# design.net
KiCad netlist of a schematic drawn in EasyEDA Pro
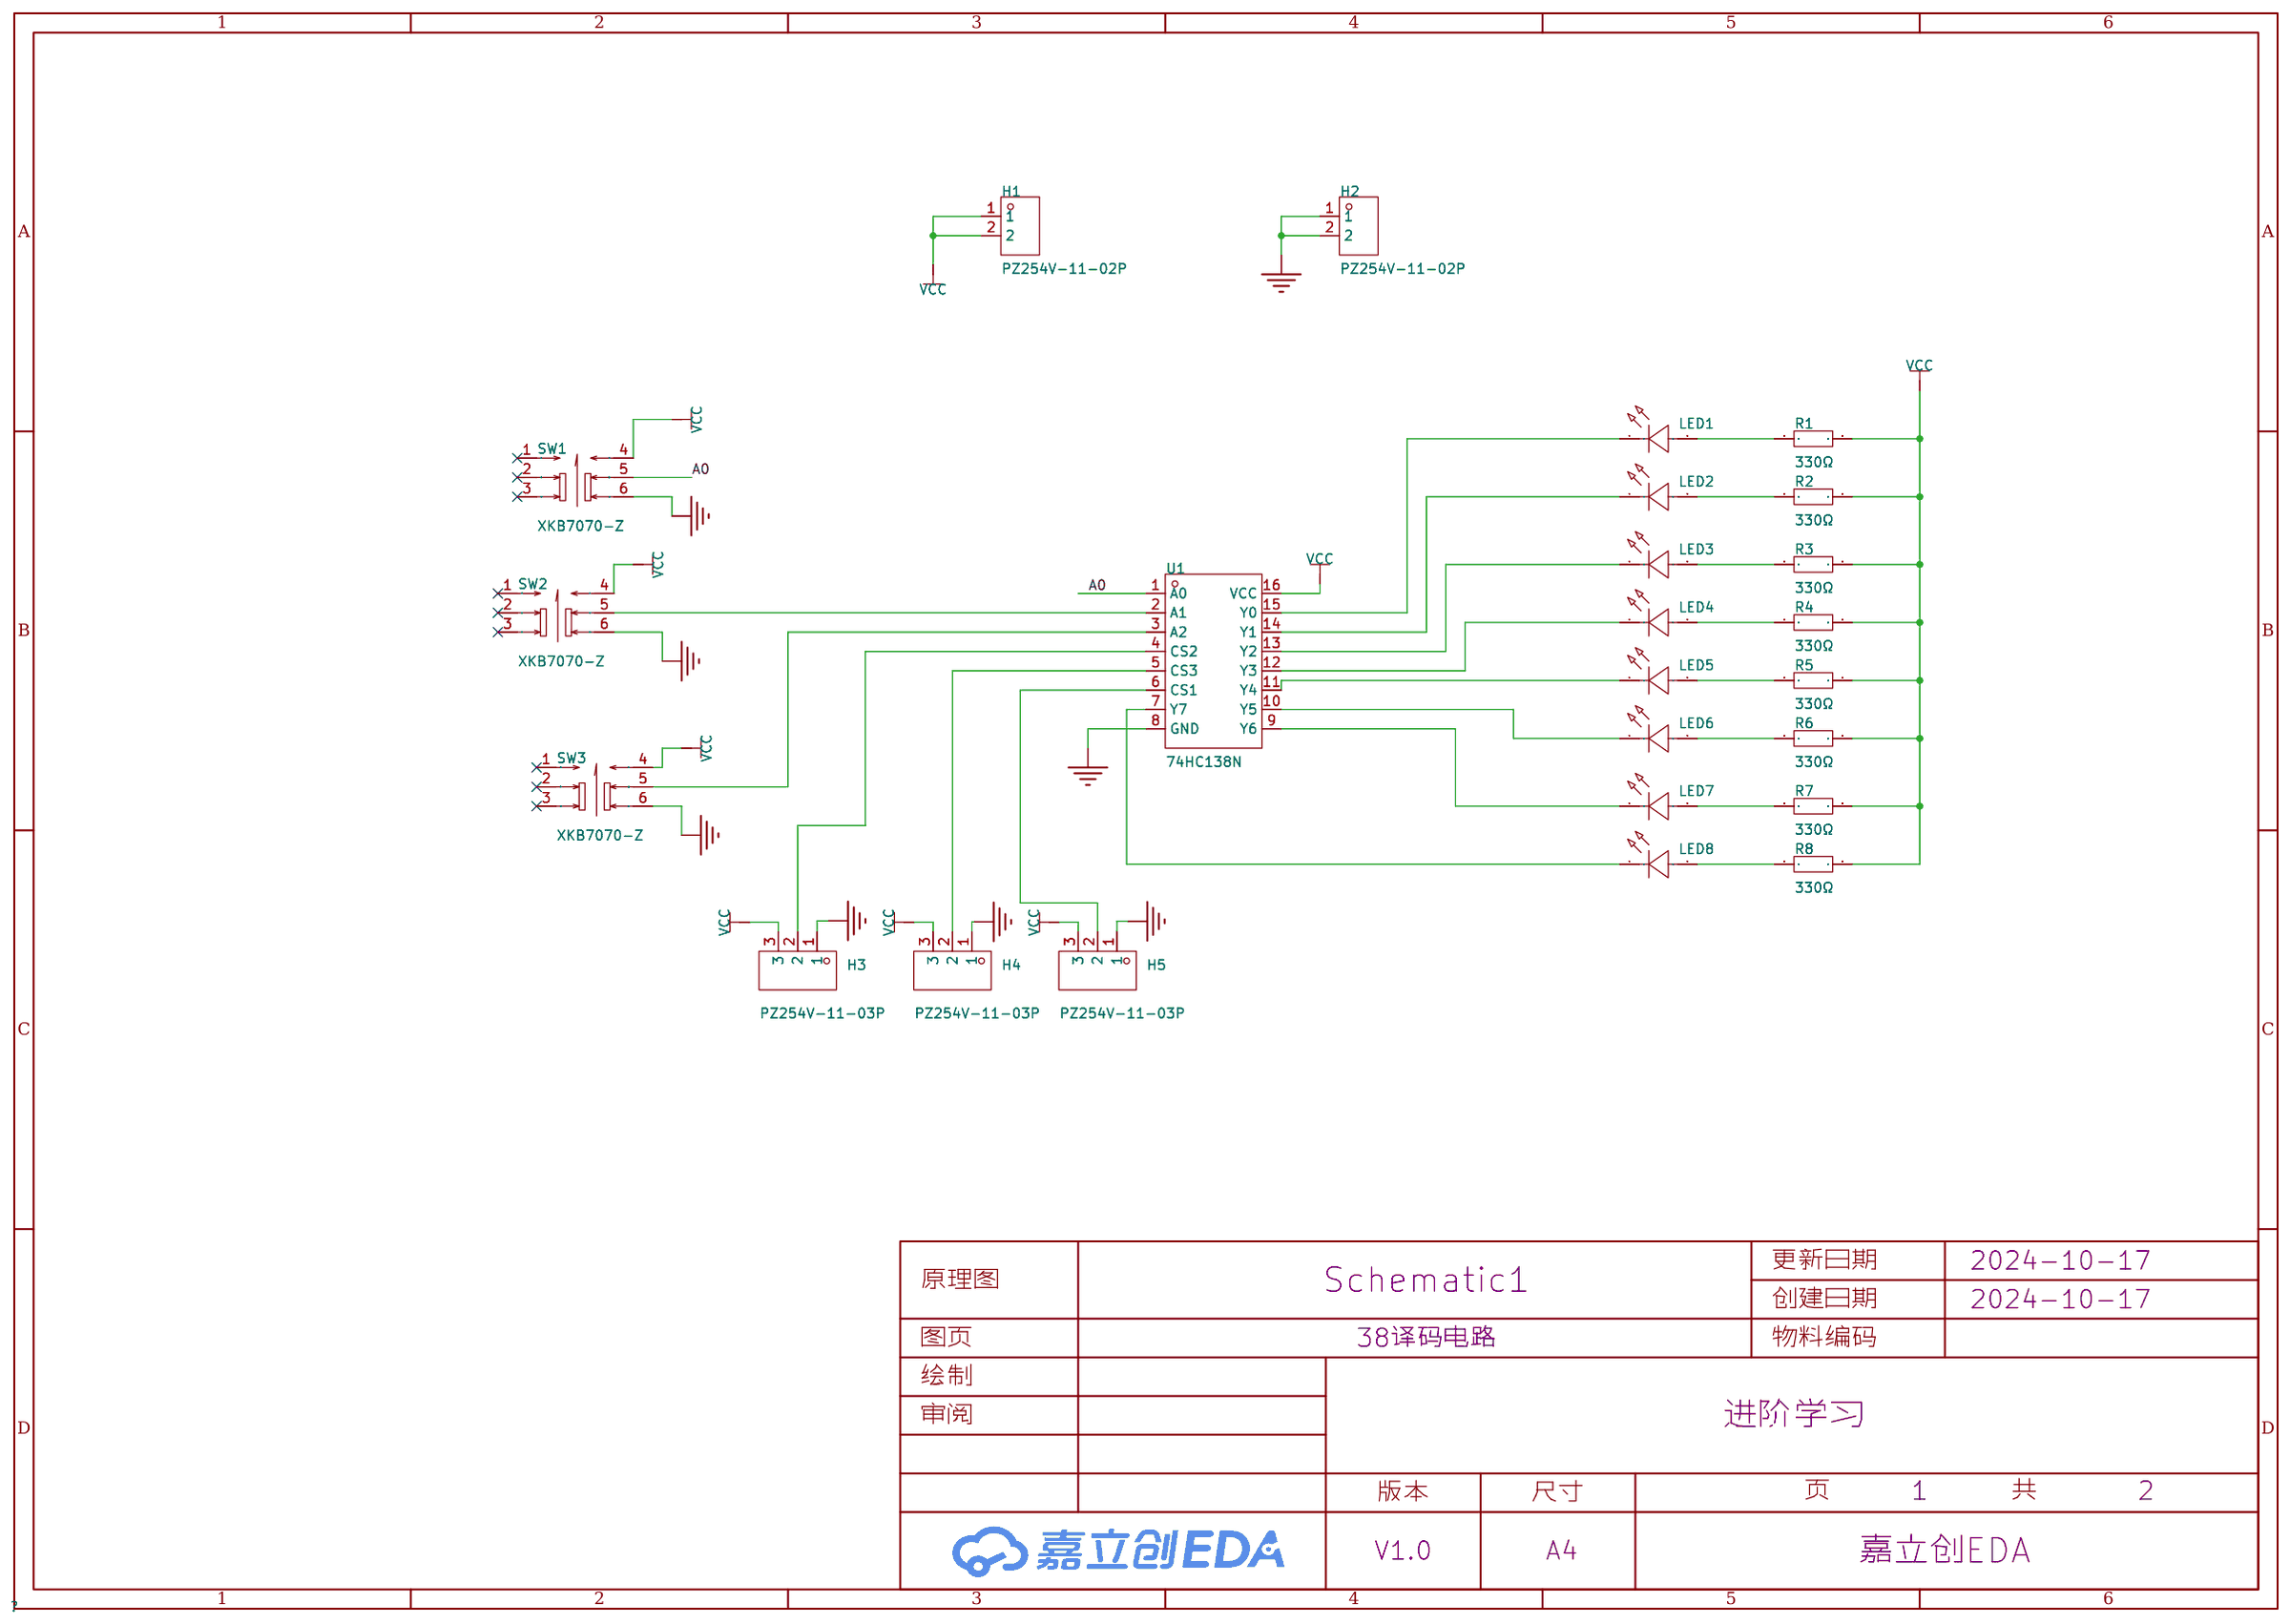
[diagram p0: 38译码电路]
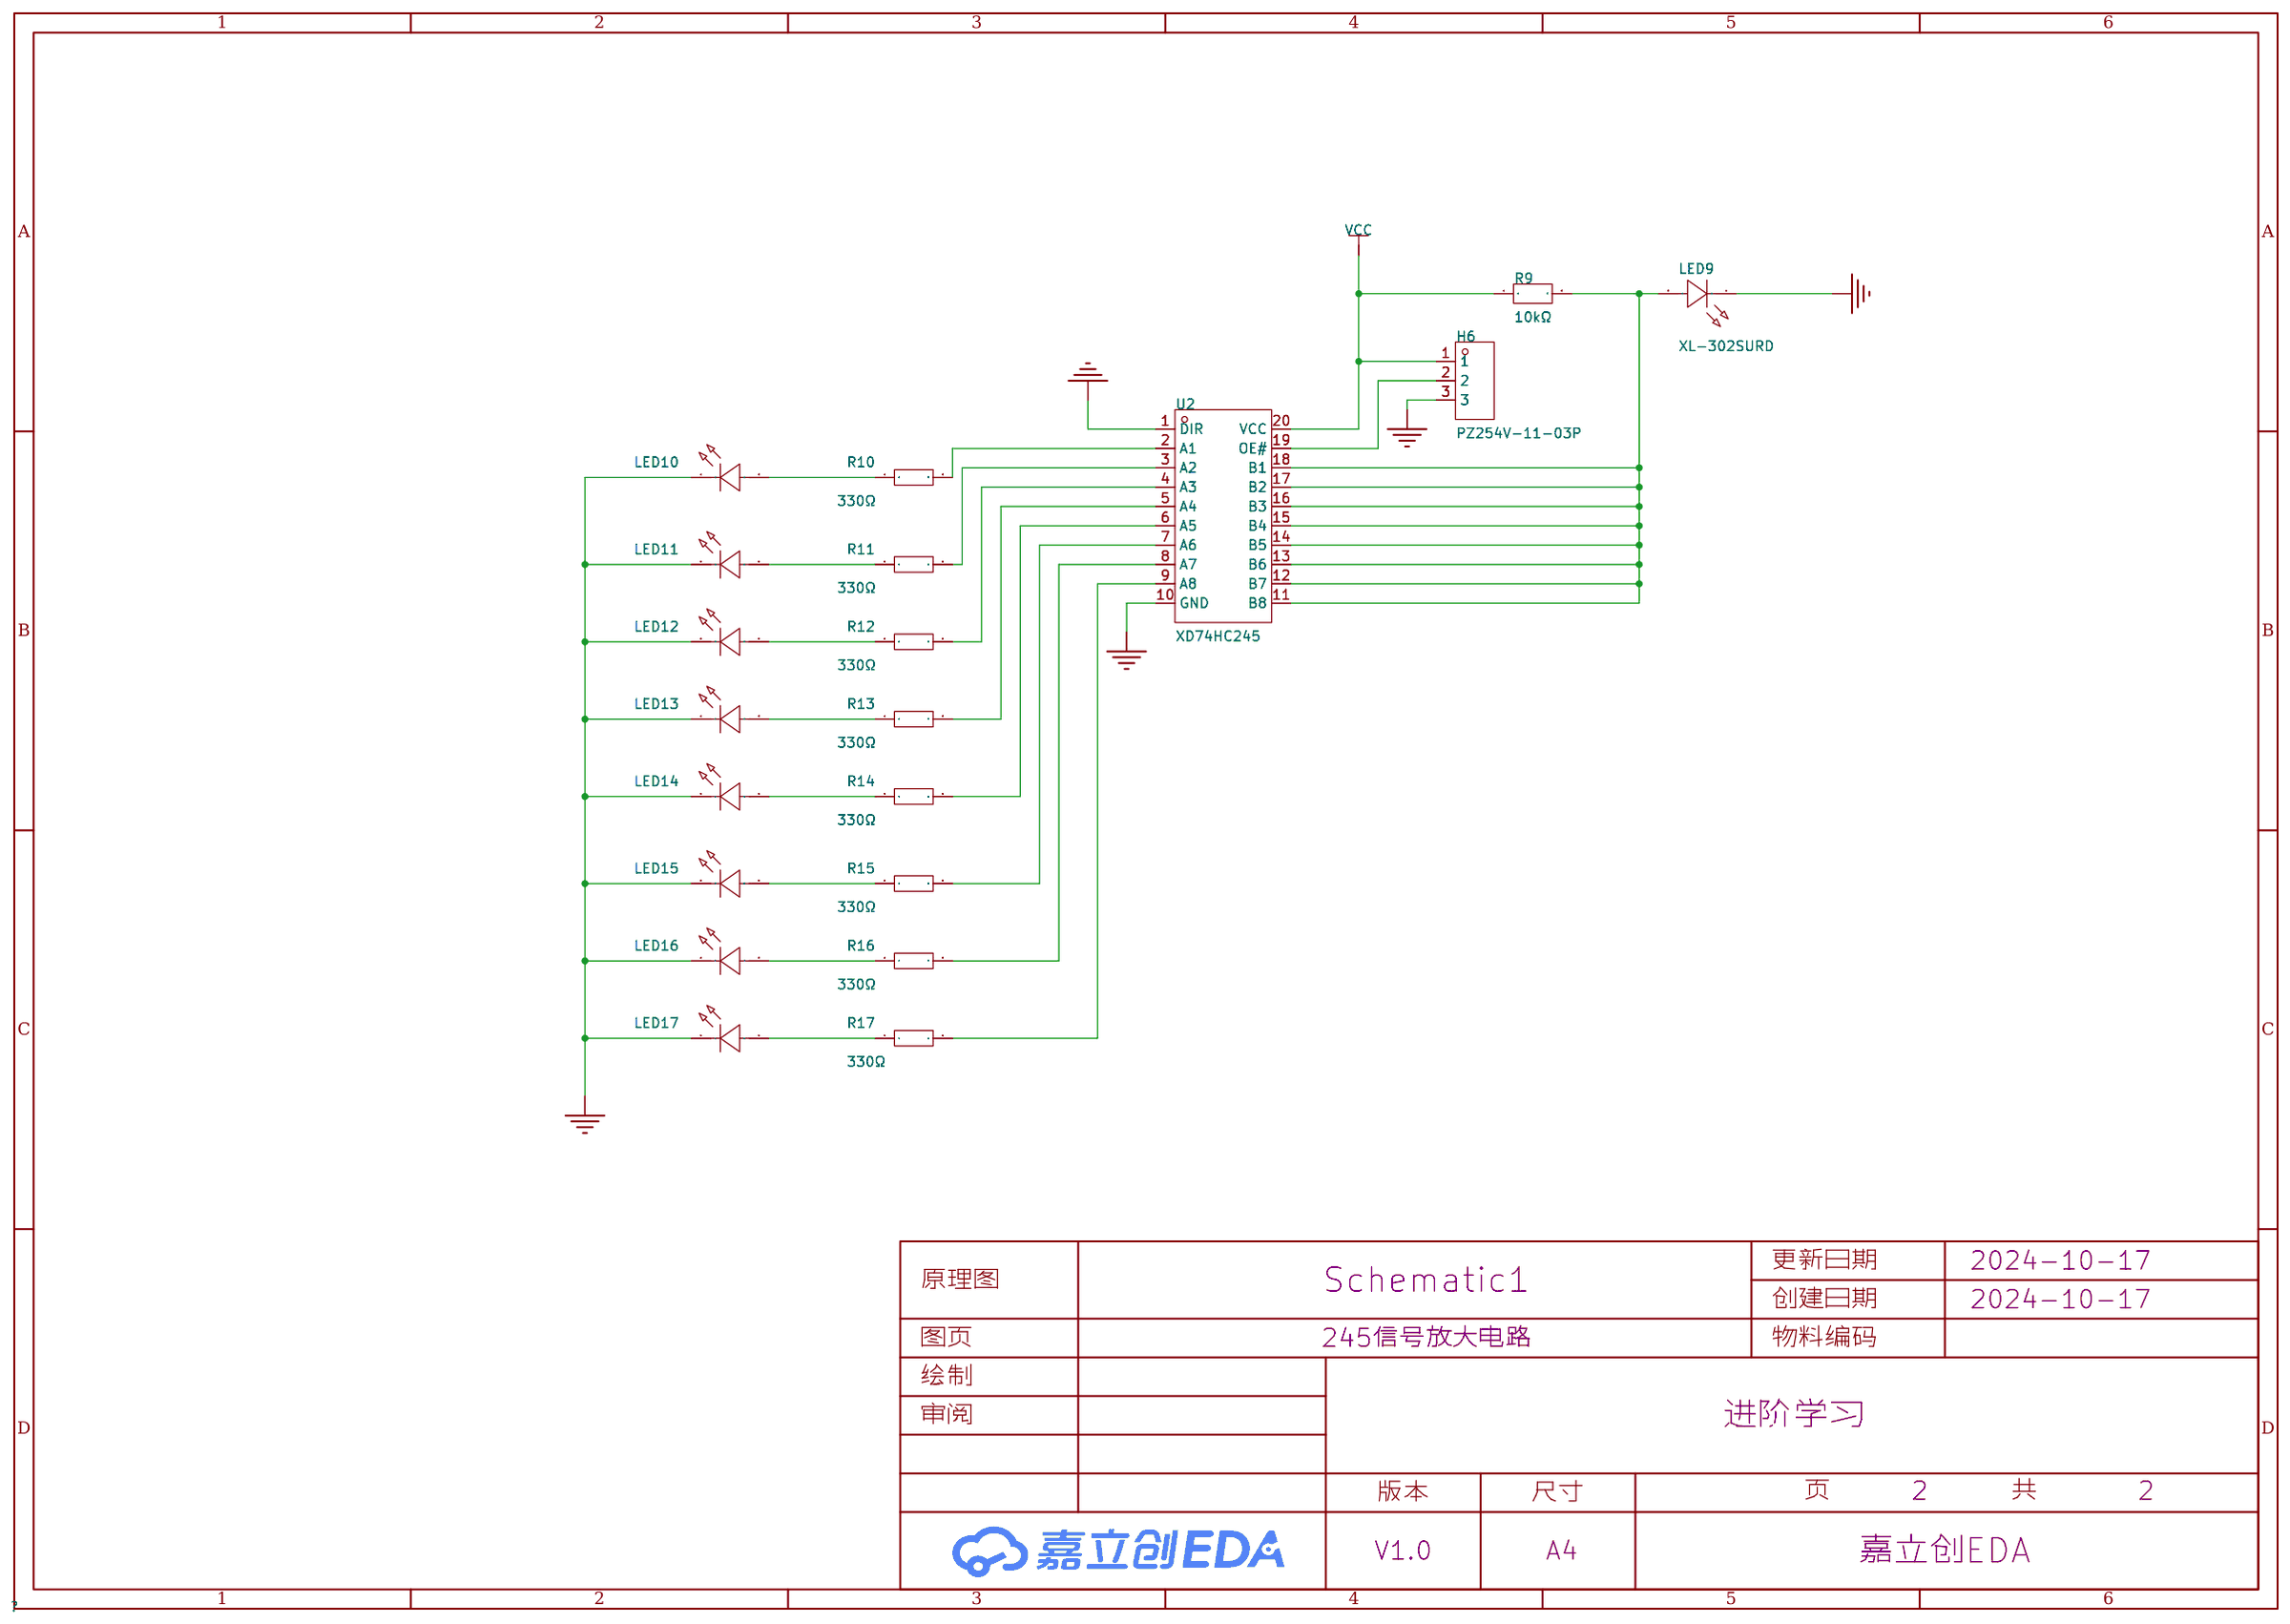
[diagram p1: 245信号放大电路]
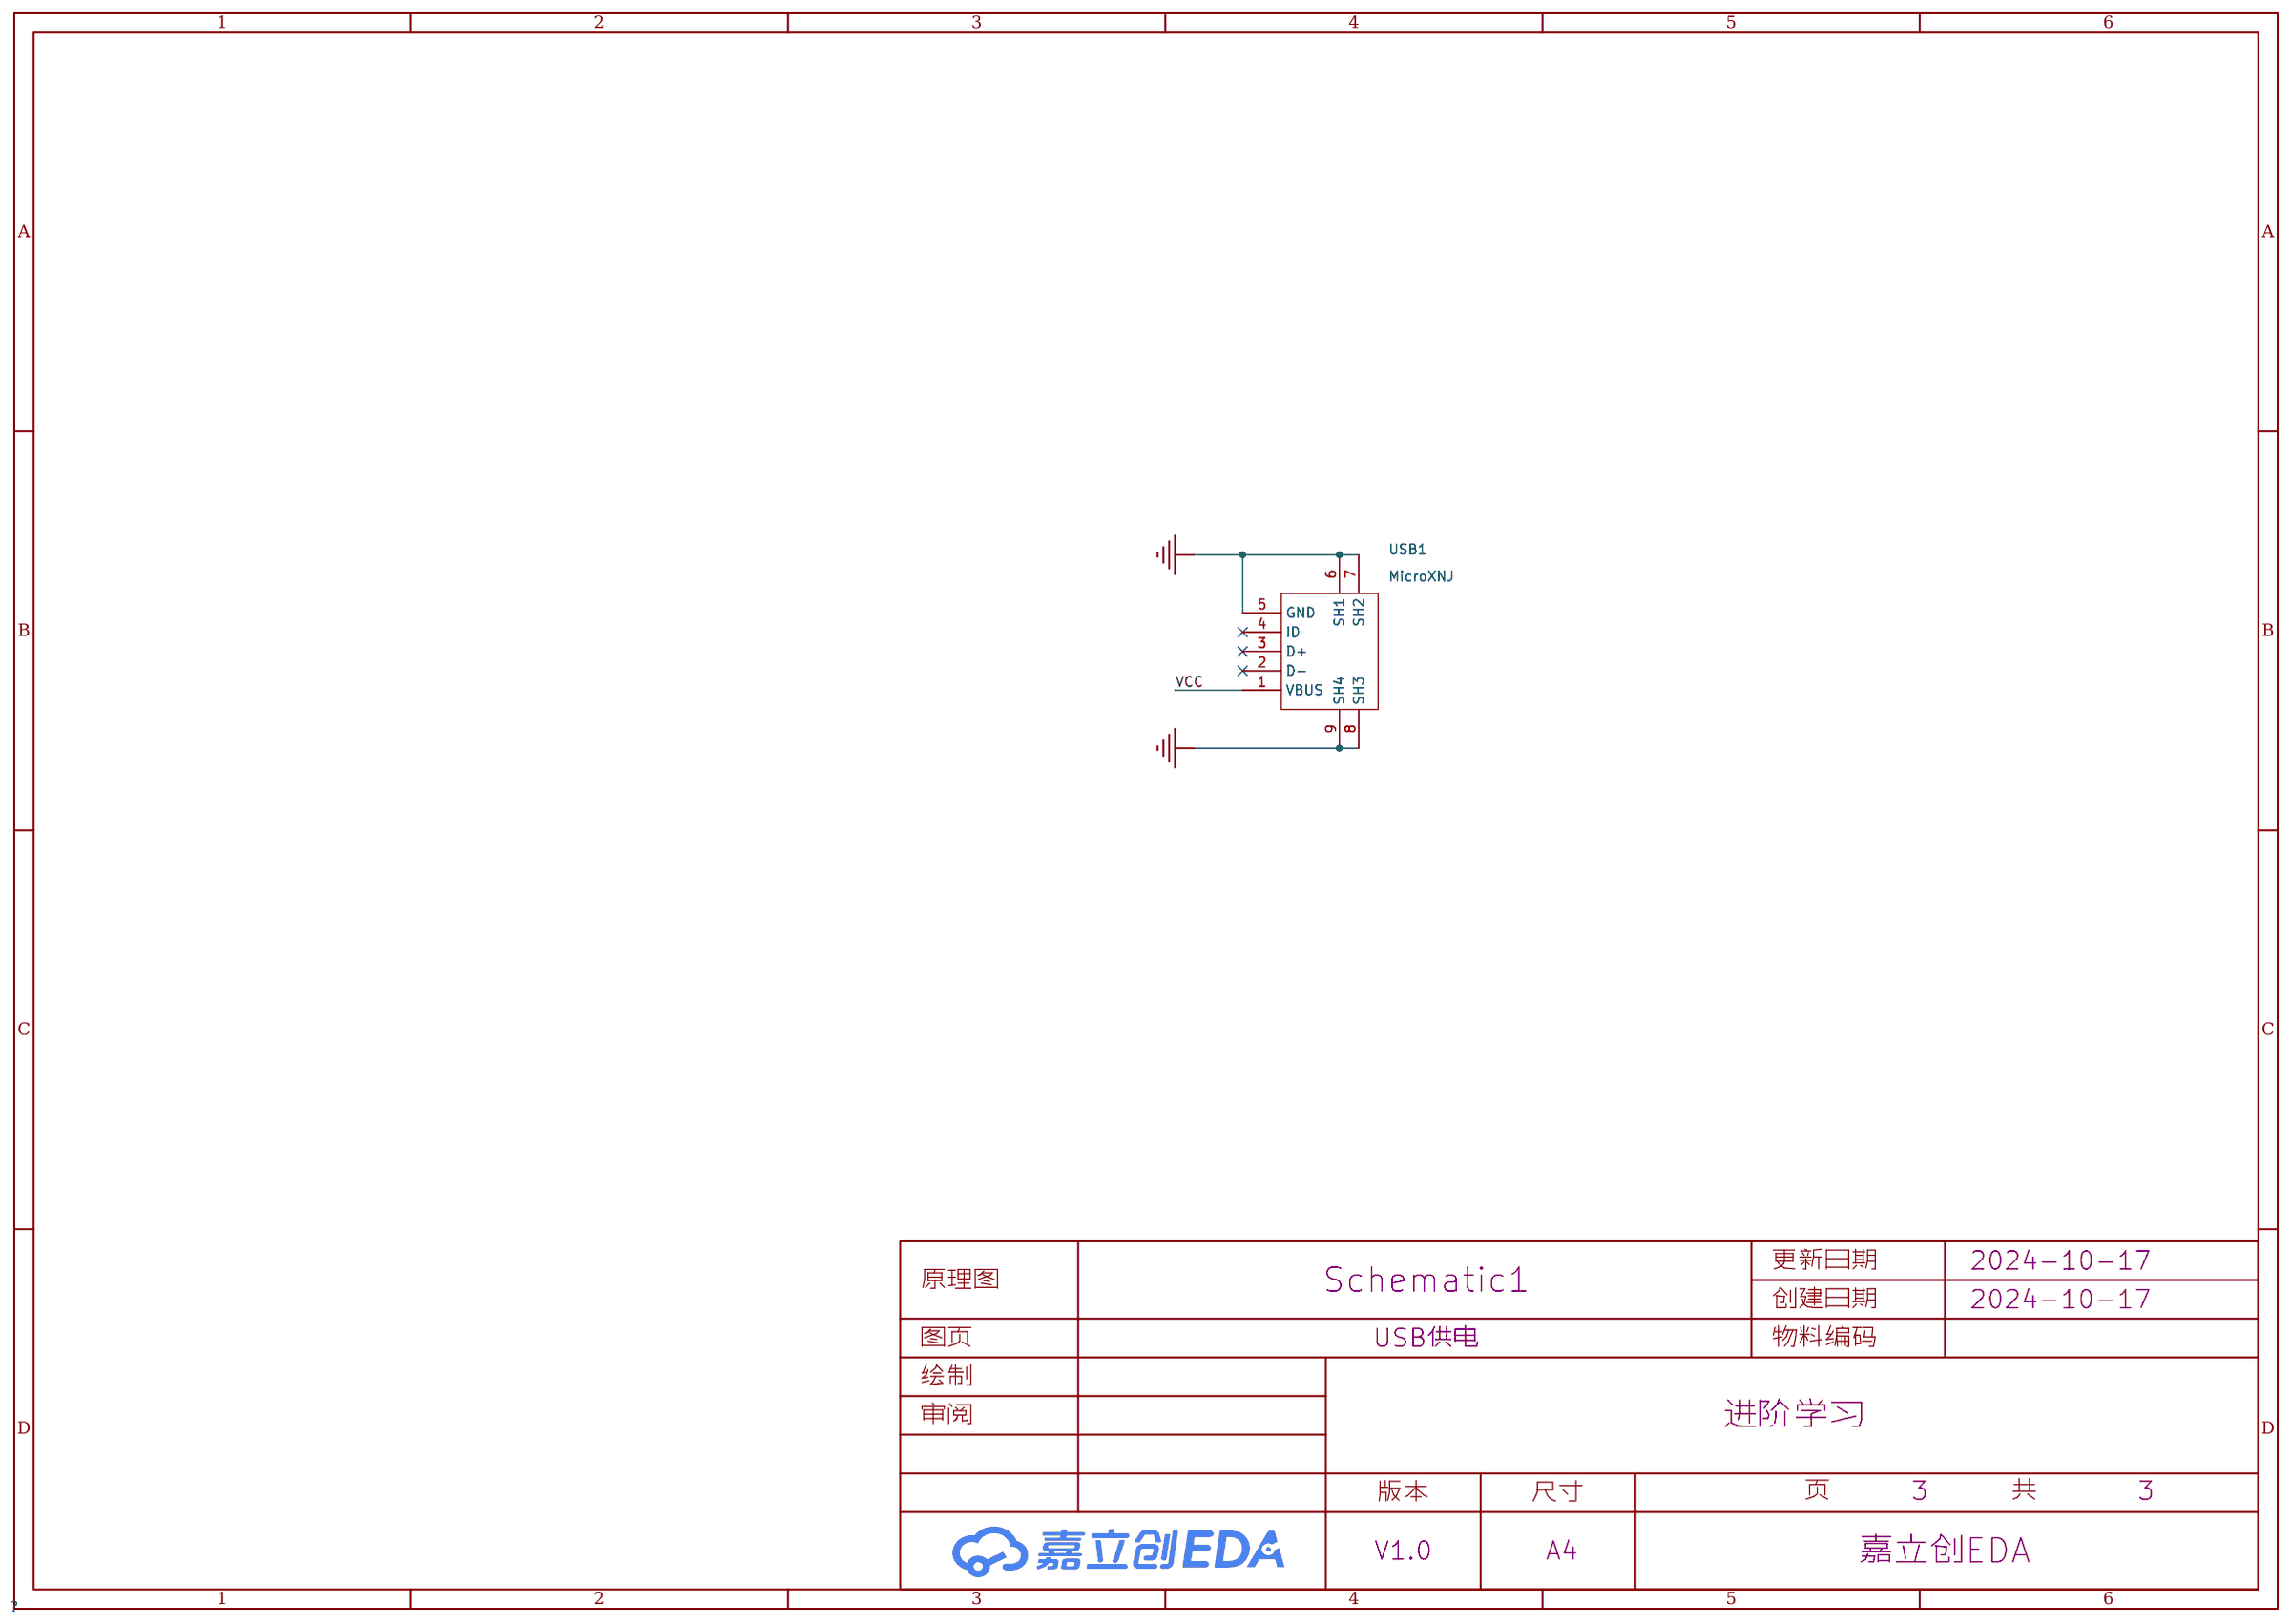
[diagram p2: USB供电]

(export (version "E")
  (design (tool "Eeschema 10.0.6"))
  (components
    (comp (ref "H1")
      (value "PZ254V-11-02P")
      (footprint "easyedapro:HDR-TH_2P-P2.54-V-M")
      (fields (field (name "Manufacturer") "XFCN(兴飞)"))
      (libsource (lib "easyedapro") (part "PZ254V-11-02P"))
    )
    (comp (ref "H2")
      (value "PZ254V-11-02P")
      (footprint "easyedapro:HDR-TH_2P-P2.54-V-M")
      (fields (field (name "Manufacturer") "XFCN(兴飞)"))
      (libsource (lib "easyedapro") (part "PZ254V-11-02P"))
    )
    (comp (ref "H3")
      (value "PZ254V-11-03P")
      (footprint "easyedapro:HDR-TH_3P-P2.54-V-M")
      (fields (field (name "Manufacturer") "XFCN(兴飞)"))
      (libsource (lib "easyedapro") (part "PZ254V-11-03P_C2937625"))
    )
    (comp (ref "H4")
      (value "PZ254V-11-03P")
      (footprint "easyedapro:HDR-TH_3P-P2.54-V-M")
      (fields (field (name "Manufacturer") "XFCN(兴飞)"))
      (libsource (lib "easyedapro") (part "PZ254V-11-03P_C2937625"))
    )
    (comp (ref "H5")
      (value "PZ254V-11-03P")
      (footprint "easyedapro:HDR-TH_3P-P2.54-V-M")
      (fields (field (name "Manufacturer") "XFCN(兴飞)"))
      (libsource (lib "easyedapro") (part "PZ254V-11-03P_C2937625"))
    )
    (comp (ref "LED1")
      (value "XL-302SURD")
      (footprint "easyedapro:LED-TH_BD3.8-P2.54-RD")
      (fields (field (name "Manufacturer") "XINGLIGHT(成兴光)"))
      (libsource (lib "easyedapro") (part "XL-302SURD"))
    )
    (comp (ref "LED2")
      (value "XL-302SURD")
      (footprint "easyedapro:LED-TH_BD3.8-P2.54-RD")
      (fields (field (name "Manufacturer") "XINGLIGHT(成兴光)"))
      (libsource (lib "easyedapro") (part "XL-302SURD"))
    )
    (comp (ref "LED3")
      (value "XL-302SURD")
      (footprint "easyedapro:LED-TH_BD3.8-P2.54-RD")
      (fields (field (name "Manufacturer") "XINGLIGHT(成兴光)"))
      (libsource (lib "easyedapro") (part "XL-302SURD"))
    )
    (comp (ref "LED4")
      (value "XL-302SURD")
      (footprint "easyedapro:LED-TH_BD3.8-P2.54-RD")
      (fields (field (name "Manufacturer") "XINGLIGHT(成兴光)"))
      (libsource (lib "easyedapro") (part "XL-302SURD"))
    )
    (comp (ref "LED5")
      (value "XL-302SURD")
      (footprint "easyedapro:LED-TH_BD3.8-P2.54-RD")
      (fields (field (name "Manufacturer") "XINGLIGHT(成兴光)"))
      (libsource (lib "easyedapro") (part "XL-302SURD"))
    )
    (comp (ref "LED6")
      (value "XL-302SURD")
      (footprint "easyedapro:LED-TH_BD3.8-P2.54-RD")
      (fields (field (name "Manufacturer") "XINGLIGHT(成兴光)"))
      (libsource (lib "easyedapro") (part "XL-302SURD"))
    )
    (comp (ref "LED7")
      (value "XL-302SURD")
      (footprint "easyedapro:LED-TH_BD3.8-P2.54-RD")
      (fields (field (name "Manufacturer") "XINGLIGHT(成兴光)"))
      (libsource (lib "easyedapro") (part "XL-302SURD"))
    )
    (comp (ref "LED8")
      (value "XL-302SURD")
      (footprint "easyedapro:LED-TH_BD3.8-P2.54-RD")
      (fields (field (name "Manufacturer") "XINGLIGHT(成兴光)"))
      (libsource (lib "easyedapro") (part "XL-302SURD"))
    )
    (comp (ref "R1")
      (value "330Ω")
      (footprint "easyedapro:RES-TH_BD2.3-L3.7-P7.70-D0.9")
      (description "电阻类型:金属膜电阻;阻值:330Ω;精度:±1%;功率:125mW;温度系数:±350ppm/°C;")
      (fields (field (name "Manufacturer Part") "MF1/8W-330Ω±1%-OT52") (field (name "Manufacturer") "VO(翔胜)"))
      (libsource (lib "easyedapro") (part "MF1/8W-330Ω±1%-OT52"))
    )
    (comp (ref "R2")
      (value "330Ω")
      (footprint "easyedapro:RES-TH_BD2.3-L3.7-P7.70-D0.9")
      (description "电阻类型:金属膜电阻;阻值:330Ω;精度:±1%;功率:125mW;温度系数:±350ppm/°C;")
      (fields (field (name "Manufacturer Part") "MF1/8W-330Ω±1%-OT52") (field (name "Manufacturer") "VO(翔胜)"))
      (libsource (lib "easyedapro") (part "MF1/8W-330Ω±1%-OT52"))
    )
    (comp (ref "R3")
      (value "330Ω")
      (footprint "easyedapro:RES-TH_BD2.3-L3.7-P7.70-D0.9")
      (description "电阻类型:金属膜电阻;阻值:330Ω;精度:±1%;功率:125mW;温度系数:±350ppm/°C;")
      (fields (field (name "Manufacturer Part") "MF1/8W-330Ω±1%-OT52") (field (name "Manufacturer") "VO(翔胜)"))
      (libsource (lib "easyedapro") (part "MF1/8W-330Ω±1%-OT52"))
    )
    (comp (ref "R4")
      (value "330Ω")
      (footprint "easyedapro:RES-TH_BD2.3-L3.7-P7.70-D0.9")
      (description "电阻类型:金属膜电阻;阻值:330Ω;精度:±1%;功率:125mW;温度系数:±350ppm/°C;")
      (fields (field (name "Manufacturer Part") "MF1/8W-330Ω±1%-OT52") (field (name "Manufacturer") "VO(翔胜)"))
      (libsource (lib "easyedapro") (part "MF1/8W-330Ω±1%-OT52"))
    )
    (comp (ref "R5")
      (value "330Ω")
      (footprint "easyedapro:RES-TH_BD2.3-L3.7-P7.70-D0.9")
      (description "电阻类型:金属膜电阻;阻值:330Ω;精度:±1%;功率:125mW;温度系数:±350ppm/°C;")
      (fields (field (name "Manufacturer Part") "MF1/8W-330Ω±1%-OT52") (field (name "Manufacturer") "VO(翔胜)"))
      (libsource (lib "easyedapro") (part "MF1/8W-330Ω±1%-OT52"))
    )
    (comp (ref "R6")
      (value "330Ω")
      (footprint "easyedapro:RES-TH_BD2.3-L3.7-P7.70-D0.9")
      (description "电阻类型:金属膜电阻;阻值:330Ω;精度:±1%;功率:125mW;温度系数:±350ppm/°C;")
      (fields (field (name "Manufacturer Part") "MF1/8W-330Ω±1%-OT52") (field (name "Manufacturer") "VO(翔胜)"))
      (libsource (lib "easyedapro") (part "MF1/8W-330Ω±1%-OT52"))
    )
    (comp (ref "R7")
      (value "330Ω")
      (footprint "easyedapro:RES-TH_BD2.3-L3.7-P7.70-D0.9")
      (description "电阻类型:金属膜电阻;阻值:330Ω;精度:±1%;功率:125mW;温度系数:±350ppm/°C;")
      (fields (field (name "Manufacturer Part") "MF1/8W-330Ω±1%-OT52") (field (name "Manufacturer") "VO(翔胜)"))
      (libsource (lib "easyedapro") (part "MF1/8W-330Ω±1%-OT52"))
    )
    (comp (ref "R8")
      (value "330Ω")
      (footprint "easyedapro:RES-TH_BD2.3-L3.7-P7.70-D0.9")
      (description "电阻类型:金属膜电阻;阻值:330Ω;精度:±1%;功率:125mW;温度系数:±350ppm/°C;")
      (fields (field (name "Manufacturer Part") "MF1/8W-330Ω±1%-OT52") (field (name "Manufacturer") "VO(翔胜)"))
      (libsource (lib "easyedapro") (part "MF1/8W-330Ω±1%-OT52"))
    )
    (comp (ref "SW1")
      (value "XKB7070-Z")
      (footprint "easyedapro:SW-TH_6P-L7.0-W7.0-P2.00")
      (description "自锁/无锁:自锁;安装方式:直插;触点电流:100mA;额定电压 (AC):250V;额定电压 (DC):30V;带灯:不带;作用力:160gf;机械寿命:10万次;")
      (fields (field (name "Manufacturer") "XKB Connectivity(中国星坤)"))
      (libsource (lib "easyedapro") (part "XKB7070-Z"))
    )
    (comp (ref "SW2")
      (value "XKB7070-Z")
      (footprint "easyedapro:SW-TH_6P-L7.0-W7.0-P2.00")
      (description "自锁/无锁:自锁;安装方式:直插;触点电流:100mA;额定电压 (AC):250V;额定电压 (DC):30V;带灯:不带;作用力:160gf;机械寿命:10万次;")
      (fields (field (name "Manufacturer") "XKB Connectivity(中国星坤)"))
      (libsource (lib "easyedapro") (part "XKB7070-Z"))
    )
    (comp (ref "SW3")
      (value "XKB7070-Z")
      (footprint "easyedapro:SW-TH_6P-L7.0-W7.0-P2.00")
      (description "自锁/无锁:自锁;安装方式:直插;触点电流:100mA;额定电压 (AC):250V;额定电压 (DC):30V;带灯:不带;作用力:160gf;机械寿命:10万次;")
      (fields (field (name "Manufacturer") "XKB Connectivity(中国星坤)"))
      (libsource (lib "easyedapro") (part "XKB7070-Z"))
    )
    (comp (ref "U1")
      (value "74HC138N")
      (footprint "easyedapro:DIP-16_L19.2-W6.6-P2.54-LS7.6-BL")
      (fields (field (name "Manufacturer") "HGSEMI(华冠)"))
      (libsource (lib "easyedapro") (part "74HC138N"))
    )
    (comp (ref "H6")
      (value "PZ254V-11-03P")
      (footprint "easyedapro:HDR-TH_3P-P2.54-V-M")
      (fields (field (name "Manufacturer") "XFCN(兴飞)"))
      (libsource (lib "easyedapro") (part "PZ254V-11-03P_C2937625"))
    )
    (comp (ref "LED9")
      (value "XL-302SURD")
      (footprint "easyedapro:LED-TH_BD3.8-P2.54-RD")
      (fields (field (name "Manufacturer") "XINGLIGHT(成兴光)"))
      (libsource (lib "easyedapro") (part "XL-302SURD"))
    )
    (comp (ref "LED10")
      (value "XL-302SURD")
      (footprint "easyedapro:LED-TH_BD3.8-P2.54-RD")
      (fields (field (name "Manufacturer") "XINGLIGHT(成兴光)"))
      (libsource (lib "easyedapro") (part "XL-302SURD"))
    )
    (comp (ref "LED11")
      (value "XL-302SURD")
      (footprint "easyedapro:LED-TH_BD3.8-P2.54-RD")
      (fields (field (name "Manufacturer") "XINGLIGHT(成兴光)"))
      (libsource (lib "easyedapro") (part "XL-302SURD"))
    )
    (comp (ref "LED12")
      (value "XL-302SURD")
      (footprint "easyedapro:LED-TH_BD3.8-P2.54-RD")
      (fields (field (name "Manufacturer") "XINGLIGHT(成兴光)"))
      (libsource (lib "easyedapro") (part "XL-302SURD"))
    )
    (comp (ref "LED13")
      (value "XL-302SURD")
      (footprint "easyedapro:LED-TH_BD3.8-P2.54-RD")
      (fields (field (name "Manufacturer") "XINGLIGHT(成兴光)"))
      (libsource (lib "easyedapro") (part "XL-302SURD"))
    )
    (comp (ref "LED14")
      (value "XL-302SURD")
      (footprint "easyedapro:LED-TH_BD3.8-P2.54-RD")
      (fields (field (name "Manufacturer") "XINGLIGHT(成兴光)"))
      (libsource (lib "easyedapro") (part "XL-302SURD"))
    )
    (comp (ref "LED15")
      (value "XL-302SURD")
      (footprint "easyedapro:LED-TH_BD3.8-P2.54-RD")
      (fields (field (name "Manufacturer") "XINGLIGHT(成兴光)"))
      (libsource (lib "easyedapro") (part "XL-302SURD"))
    )
    (comp (ref "LED16")
      (value "XL-302SURD")
      (footprint "easyedapro:LED-TH_BD3.8-P2.54-RD")
      (fields (field (name "Manufacturer") "XINGLIGHT(成兴光)"))
      (libsource (lib "easyedapro") (part "XL-302SURD"))
    )
    (comp (ref "LED17")
      (value "XL-302SURD")
      (footprint "easyedapro:LED-TH_BD3.8-P2.54-RD")
      (fields (field (name "Manufacturer") "XINGLIGHT(成兴光)"))
      (libsource (lib "easyedapro") (part "XL-302SURD"))
    )
    (comp (ref "R9")
      (value "10kΩ")
      (footprint "easyedapro:RES-TH_BD1.8-L3.2-P7.20-D0.4")
      (description "电阻类型:金属膜电阻;阻值:10kΩ;精度:±1%;功率:125mW;温度系数:±200ppm/°C;")
      (fields (field (name "Manufacturer Part") "MF1/8W-10KΩ±1%T52") (field (name "Manufacturer") "华星机电"))
      (libsource (lib "easyedapro") (part "MF1/8W-10KΩ±1%T52"))
    )
    (comp (ref "R10")
      (value "330Ω")
      (footprint "easyedapro:RES-TH_BD2.3-L3.7-P7.70-D0.9")
      (description "电阻类型:金属膜电阻;阻值:330Ω;精度:±1%;功率:125mW;温度系数:±350ppm/°C;")
      (fields (field (name "Manufacturer Part") "MF1/8W-330Ω±1%-OT52") (field (name "Manufacturer") "VO(翔胜)"))
      (libsource (lib "easyedapro") (part "MF1/8W-330Ω±1%-OT52"))
    )
    (comp (ref "R11")
      (value "330Ω")
      (footprint "easyedapro:RES-TH_BD2.3-L3.7-P7.70-D0.9")
      (description "电阻类型:金属膜电阻;阻值:330Ω;精度:±1%;功率:125mW;温度系数:±350ppm/°C;")
      (fields (field (name "Manufacturer Part") "MF1/8W-330Ω±1%-OT52") (field (name "Manufacturer") "VO(翔胜)"))
      (libsource (lib "easyedapro") (part "MF1/8W-330Ω±1%-OT52"))
    )
    (comp (ref "R12")
      (value "330Ω")
      (footprint "easyedapro:RES-TH_BD2.3-L3.7-P7.70-D0.9")
      (description "电阻类型:金属膜电阻;阻值:330Ω;精度:±1%;功率:125mW;温度系数:±350ppm/°C;")
      (fields (field (name "Manufacturer Part") "MF1/8W-330Ω±1%-OT52") (field (name "Manufacturer") "VO(翔胜)"))
      (libsource (lib "easyedapro") (part "MF1/8W-330Ω±1%-OT52"))
    )
    (comp (ref "R13")
      (value "330Ω")
      (footprint "easyedapro:RES-TH_BD2.3-L3.7-P7.70-D0.9")
      (description "电阻类型:金属膜电阻;阻值:330Ω;精度:±1%;功率:125mW;温度系数:±350ppm/°C;")
      (fields (field (name "Manufacturer Part") "MF1/8W-330Ω±1%-OT52") (field (name "Manufacturer") "VO(翔胜)"))
      (libsource (lib "easyedapro") (part "MF1/8W-330Ω±1%-OT52"))
    )
    (comp (ref "R14")
      (value "330Ω")
      (footprint "easyedapro:RES-TH_BD2.3-L3.7-P7.70-D0.9")
      (description "电阻类型:金属膜电阻;阻值:330Ω;精度:±1%;功率:125mW;温度系数:±350ppm/°C;")
      (fields (field (name "Manufacturer Part") "MF1/8W-330Ω±1%-OT52") (field (name "Manufacturer") "VO(翔胜)"))
      (libsource (lib "easyedapro") (part "MF1/8W-330Ω±1%-OT52"))
    )
    (comp (ref "R15")
      (value "330Ω")
      (footprint "easyedapro:RES-TH_BD2.3-L3.7-P7.70-D0.9")
      (description "电阻类型:金属膜电阻;阻值:330Ω;精度:±1%;功率:125mW;温度系数:±350ppm/°C;")
      (fields (field (name "Manufacturer Part") "MF1/8W-330Ω±1%-OT52") (field (name "Manufacturer") "VO(翔胜)"))
      (libsource (lib "easyedapro") (part "MF1/8W-330Ω±1%-OT52"))
    )
    (comp (ref "R16")
      (value "330Ω")
      (footprint "easyedapro:RES-TH_BD2.3-L3.7-P7.70-D0.9")
      (description "电阻类型:金属膜电阻;阻值:330Ω;精度:±1%;功率:125mW;温度系数:±350ppm/°C;")
      (fields (field (name "Manufacturer Part") "MF1/8W-330Ω±1%-OT52") (field (name "Manufacturer") "VO(翔胜)"))
      (libsource (lib "easyedapro") (part "MF1/8W-330Ω±1%-OT52"))
    )
    (comp (ref "R17")
      (value "330Ω")
      (footprint "easyedapro:RES-TH_BD2.3-L3.7-P7.70-D0.9")
      (description "电阻类型:金属膜电阻;阻值:330Ω;精度:±1%;功率:125mW;温度系数:±350ppm/°C;")
      (fields (field (name "Manufacturer Part") "MF1/8W-330Ω±1%-OT52") (field (name "Manufacturer") "VO(翔胜)"))
      (libsource (lib "easyedapro") (part "MF1/8W-330Ω±1%-OT52"))
    )
    (comp (ref "U2")
      (value "XD74HC245")
      (footprint "easyedapro:DIP-20_L26.8-W6.4-P2.54-LS7.6-BL")
      (fields (field (name "Manufacturer") "XINLUDA(信路达)"))
      (libsource (lib "easyedapro") (part "XD74HC245"))
    )
    (comp (ref "USB1")
      (value "MicroXNJ")
      (footprint "easyedapro:MICRO-USB-SMD_MICROXNJ")
      (description "连接器类型:Micro-B;标准:USB 2.0;公母:母;安装方式:卧贴;触点数量:5P;端口数量:1;额定电流 - 电源:1.8A;工作温度范围:-20°C~+85°C;")
      (fields (field (name "Manufacturer") "SHOU HAN(首韩)"))
      (libsource (lib "easyedapro") (part "MICROXNJ"))
    )
  )
  (nets
    (net (code "1") (name "A0") (class "Default")
      (node (ref "SW1") (pin "5") (pinfunction "5_5") (pintype "unspecified"))
      (node (ref "U1") (pin "1") (pinfunction "A0_1") (pintype "input"))
    )
    (net (code "2") (name "GND") (class "Default")
      (node (ref "H2") (pin "1") (pinfunction "1_1") (pintype "unspecified"))
      (node (ref "H2") (pin "2") (pinfunction "2_2") (pintype "unspecified"))
      (node (ref "H3") (pin "1") (pinfunction "1_1") (pintype "unspecified"))
      (node (ref "H4") (pin "1") (pinfunction "1_1") (pintype "unspecified"))
      (node (ref "H5") (pin "1") (pinfunction "1_1") (pintype "unspecified"))
      (node (ref "H6") (pin "3") (pinfunction "3_3") (pintype "unspecified"))
      (node (ref "LED10") (pin "1") (pinfunction "K_1") (pintype "unspecified"))
      (node (ref "LED11") (pin "1") (pinfunction "K_1") (pintype "unspecified"))
      (node (ref "LED12") (pin "1") (pinfunction "K_1") (pintype "unspecified"))
      (node (ref "LED13") (pin "1") (pinfunction "K_1") (pintype "unspecified"))
      (node (ref "LED14") (pin "1") (pinfunction "K_1") (pintype "unspecified"))
      (node (ref "LED15") (pin "1") (pinfunction "K_1") (pintype "unspecified"))
      (node (ref "LED16") (pin "1") (pinfunction "K_1") (pintype "unspecified"))
      (node (ref "LED17") (pin "1") (pinfunction "K_1") (pintype "unspecified"))
      (node (ref "LED9") (pin "1") (pinfunction "K_1") (pintype "unspecified"))
      (node (ref "SW1") (pin "6") (pinfunction "6_6") (pintype "unspecified"))
      (node (ref "SW2") (pin "6") (pinfunction "6_6") (pintype "unspecified"))
      (node (ref "SW3") (pin "6") (pinfunction "6_6") (pintype "unspecified"))
      (node (ref "U1") (pin "8") (pinfunction "GND_8") (pintype "input"))
      (node (ref "U2") (pin "1") (pinfunction "DIR_1") (pintype "unspecified"))
      (node (ref "U2") (pin "10") (pinfunction "GND_10") (pintype "unspecified"))
      (node (ref "USB1") (pin "5") (pinfunction "GND_5") (pintype "unspecified"))
      (node (ref "USB1") (pin "6") (pinfunction "SH1_6") (pintype "unspecified"))
      (node (ref "USB1") (pin "7") (pinfunction "SH2_7") (pintype "unspecified"))
      (node (ref "USB1") (pin "8") (pinfunction "SH3_8") (pintype "unspecified"))
      (node (ref "USB1") (pin "9") (pinfunction "SH4_9") (pintype "unspecified"))
    )
    (net (code "3") (name "Net-(LED1-A)") (class "Default")
      (node (ref "LED1") (pin "2") (pinfunction "A_2") (pintype "unspecified"))
      (node (ref "R1") (pin "1") (pinfunction "1_1") (pintype "unspecified"))
    )
    (net (code "4") (name "Net-(LED1-K)") (class "Default")
      (node (ref "LED1") (pin "1") (pinfunction "K_1") (pintype "unspecified"))
      (node (ref "U1") (pin "15") (pinfunction "Y0_15") (pintype "input"))
    )
    (net (code "5") (name "Net-(LED2-A)") (class "Default")
      (node (ref "LED2") (pin "2") (pinfunction "A_2") (pintype "unspecified"))
      (node (ref "R2") (pin "1") (pinfunction "1_1") (pintype "unspecified"))
    )
    (net (code "6") (name "Net-(LED2-K)") (class "Default")
      (node (ref "LED2") (pin "1") (pinfunction "K_1") (pintype "unspecified"))
      (node (ref "U1") (pin "14") (pinfunction "Y1_14") (pintype "input"))
    )
    (net (code "7") (name "Net-(LED3-A)") (class "Default")
      (node (ref "LED3") (pin "2") (pinfunction "A_2") (pintype "unspecified"))
      (node (ref "R3") (pin "1") (pinfunction "1_1") (pintype "unspecified"))
    )
    (net (code "8") (name "Net-(LED3-K)") (class "Default")
      (node (ref "LED3") (pin "1") (pinfunction "K_1") (pintype "unspecified"))
      (node (ref "U1") (pin "13") (pinfunction "Y2_13") (pintype "input"))
    )
    (net (code "9") (name "Net-(LED4-A)") (class "Default")
      (node (ref "LED4") (pin "2") (pinfunction "A_2") (pintype "unspecified"))
      (node (ref "R4") (pin "1") (pinfunction "1_1") (pintype "unspecified"))
    )
    (net (code "10") (name "Net-(LED4-K)") (class "Default")
      (node (ref "LED4") (pin "1") (pinfunction "K_1") (pintype "unspecified"))
      (node (ref "U1") (pin "12") (pinfunction "Y3_12") (pintype "input"))
    )
    (net (code "11") (name "Net-(LED5-A)") (class "Default")
      (node (ref "LED5") (pin "2") (pinfunction "A_2") (pintype "unspecified"))
      (node (ref "R5") (pin "1") (pinfunction "1_1") (pintype "unspecified"))
    )
    (net (code "12") (name "Net-(LED5-K)") (class "Default")
      (node (ref "LED5") (pin "1") (pinfunction "K_1") (pintype "unspecified"))
      (node (ref "U1") (pin "11") (pinfunction "Y4_11") (pintype "input"))
    )
    (net (code "13") (name "Net-(LED6-A)") (class "Default")
      (node (ref "LED6") (pin "2") (pinfunction "A_2") (pintype "unspecified"))
      (node (ref "R6") (pin "1") (pinfunction "1_1") (pintype "unspecified"))
    )
    (net (code "14") (name "Net-(LED6-K)") (class "Default")
      (node (ref "LED6") (pin "1") (pinfunction "K_1") (pintype "unspecified"))
      (node (ref "U1") (pin "10") (pinfunction "Y5_10") (pintype "input"))
    )
    (net (code "15") (name "Net-(LED7-A)") (class "Default")
      (node (ref "LED7") (pin "2") (pinfunction "A_2") (pintype "unspecified"))
      (node (ref "R7") (pin "1") (pinfunction "1_1") (pintype "unspecified"))
    )
    (net (code "16") (name "Net-(LED7-K)") (class "Default")
      (node (ref "LED7") (pin "1") (pinfunction "K_1") (pintype "unspecified"))
      (node (ref "U1") (pin "9") (pinfunction "Y6_9") (pintype "input"))
    )
    (net (code "17") (name "Net-(LED8-A)") (class "Default")
      (node (ref "LED8") (pin "2") (pinfunction "A_2") (pintype "unspecified"))
      (node (ref "R8") (pin "1") (pinfunction "1_1") (pintype "unspecified"))
    )
    (net (code "18") (name "Net-(LED8-K)") (class "Default")
      (node (ref "LED8") (pin "1") (pinfunction "K_1") (pintype "unspecified"))
      (node (ref "U1") (pin "7") (pinfunction "Y7_7") (pintype "input"))
    )
    (net (code "19") (name "Net-(LED9-A)") (class "Default")
      (node (ref "LED9") (pin "2") (pinfunction "A_2") (pintype "unspecified"))
      (node (ref "R9") (pin "2") (pinfunction "2_2") (pintype "unspecified"))
      (node (ref "U2") (pin "11") (pinfunction "B8_11") (pintype "unspecified"))
      (node (ref "U2") (pin "12") (pinfunction "B7_12") (pintype "unspecified"))
      (node (ref "U2") (pin "13") (pinfunction "B6_13") (pintype "unspecified"))
      (node (ref "U2") (pin "14") (pinfunction "B5_14") (pintype "unspecified"))
      (node (ref "U2") (pin "15") (pinfunction "B4_15") (pintype "unspecified"))
      (node (ref "U2") (pin "16") (pinfunction "B3_16") (pintype "unspecified"))
      (node (ref "U2") (pin "17") (pinfunction "B2_17") (pintype "unspecified"))
      (node (ref "U2") (pin "18") (pinfunction "B1_18") (pintype "unspecified"))
    )
    (net (code "20") (name "Net-(LED10-A)") (class "Default")
      (node (ref "LED10") (pin "2") (pinfunction "A_2") (pintype "unspecified"))
      (node (ref "R10") (pin "1") (pinfunction "1_1") (pintype "unspecified"))
    )
    (net (code "21") (name "Net-(LED11-A)") (class "Default")
      (node (ref "LED11") (pin "2") (pinfunction "A_2") (pintype "unspecified"))
      (node (ref "R11") (pin "1") (pinfunction "1_1") (pintype "unspecified"))
    )
    (net (code "22") (name "Net-(LED12-A)") (class "Default")
      (node (ref "LED12") (pin "2") (pinfunction "A_2") (pintype "unspecified"))
      (node (ref "R12") (pin "1") (pinfunction "1_1") (pintype "unspecified"))
    )
    (net (code "23") (name "Net-(LED13-A)") (class "Default")
      (node (ref "LED13") (pin "2") (pinfunction "A_2") (pintype "unspecified"))
      (node (ref "R13") (pin "1") (pinfunction "1_1") (pintype "unspecified"))
    )
    (net (code "24") (name "Net-(LED14-A)") (class "Default")
      (node (ref "LED14") (pin "2") (pinfunction "A_2") (pintype "unspecified"))
      (node (ref "R14") (pin "1") (pinfunction "1_1") (pintype "unspecified"))
    )
    (net (code "25") (name "Net-(LED15-A)") (class "Default")
      (node (ref "LED15") (pin "2") (pinfunction "A_2") (pintype "unspecified"))
      (node (ref "R15") (pin "1") (pinfunction "1_1") (pintype "unspecified"))
    )
    (net (code "26") (name "Net-(LED16-A)") (class "Default")
      (node (ref "LED16") (pin "2") (pinfunction "A_2") (pintype "unspecified"))
      (node (ref "R16") (pin "1") (pinfunction "1_1") (pintype "unspecified"))
    )
    (net (code "27") (name "Net-(LED17-A)") (class "Default")
      (node (ref "LED17") (pin "2") (pinfunction "A_2") (pintype "unspecified"))
      (node (ref "R17") (pin "1") (pinfunction "1_1") (pintype "unspecified"))
    )
    (net (code "28") (name "Net-(U1-A1)") (class "Default")
      (node (ref "SW2") (pin "5") (pinfunction "5_5") (pintype "unspecified"))
      (node (ref "U1") (pin "2") (pinfunction "A1_2") (pintype "input"))
    )
    (net (code "29") (name "Net-(U1-A2)") (class "Default")
      (node (ref "SW3") (pin "5") (pinfunction "5_5") (pintype "unspecified"))
      (node (ref "U1") (pin "3") (pinfunction "A2_3") (pintype "input"))
    )
    (net (code "30") (name "Net-(U1-CS1)") (class "Default")
      (node (ref "H5") (pin "2") (pinfunction "2_2") (pintype "unspecified"))
      (node (ref "U1") (pin "6") (pinfunction "CS1_6") (pintype "input"))
    )
    (net (code "31") (name "Net-(U1-CS2)") (class "Default")
      (node (ref "H3") (pin "2") (pinfunction "2_2") (pintype "unspecified"))
      (node (ref "U1") (pin "4") (pinfunction "CS2_4") (pintype "input"))
    )
    (net (code "32") (name "Net-(U1-CS3)") (class "Default")
      (node (ref "H4") (pin "2") (pinfunction "2_2") (pintype "unspecified"))
      (node (ref "U1") (pin "5") (pinfunction "CS3_5") (pintype "input"))
    )
    (net (code "33") (name "Net-(U2-A1)") (class "Default")
      (node (ref "R10") (pin "2") (pinfunction "2_2") (pintype "unspecified"))
      (node (ref "U2") (pin "2") (pinfunction "A1_2") (pintype "unspecified"))
    )
    (net (code "34") (name "Net-(U2-A2)") (class "Default")
      (node (ref "R11") (pin "2") (pinfunction "2_2") (pintype "unspecified"))
      (node (ref "U2") (pin "3") (pinfunction "A2_3") (pintype "unspecified"))
    )
    (net (code "35") (name "Net-(U2-A3)") (class "Default")
      (node (ref "R12") (pin "2") (pinfunction "2_2") (pintype "unspecified"))
      (node (ref "U2") (pin "4") (pinfunction "A3_4") (pintype "unspecified"))
    )
    (net (code "36") (name "Net-(U2-A4)") (class "Default")
      (node (ref "R13") (pin "2") (pinfunction "2_2") (pintype "unspecified"))
      (node (ref "U2") (pin "5") (pinfunction "A4_5") (pintype "unspecified"))
    )
    (net (code "37") (name "Net-(U2-A5)") (class "Default")
      (node (ref "R14") (pin "2") (pinfunction "2_2") (pintype "unspecified"))
      (node (ref "U2") (pin "6") (pinfunction "A5_6") (pintype "unspecified"))
    )
    (net (code "38") (name "Net-(U2-A6)") (class "Default")
      (node (ref "R15") (pin "2") (pinfunction "2_2") (pintype "unspecified"))
      (node (ref "U2") (pin "7") (pinfunction "A6_7") (pintype "unspecified"))
    )
    (net (code "39") (name "Net-(U2-A7)") (class "Default")
      (node (ref "R16") (pin "2") (pinfunction "2_2") (pintype "unspecified"))
      (node (ref "U2") (pin "8") (pinfunction "A7_8") (pintype "unspecified"))
    )
    (net (code "40") (name "Net-(U2-A8)") (class "Default")
      (node (ref "R17") (pin "2") (pinfunction "2_2") (pintype "unspecified"))
      (node (ref "U2") (pin "9") (pinfunction "A8_9") (pintype "unspecified"))
    )
    (net (code "41") (name "Net-(U2-OE#)") (class "Default")
      (node (ref "H6") (pin "2") (pinfunction "2_2") (pintype "unspecified"))
      (node (ref "U2") (pin "19") (pinfunction "OE#_19") (pintype "unspecified"))
    )
    (net (code "42") (name "VCC") (class "Default")
      (node (ref "H1") (pin "1") (pinfunction "1_1") (pintype "unspecified"))
      (node (ref "H1") (pin "2") (pinfunction "2_2") (pintype "unspecified"))
      (node (ref "H3") (pin "3") (pinfunction "3_3") (pintype "unspecified"))
      (node (ref "H4") (pin "3") (pinfunction "3_3") (pintype "unspecified"))
      (node (ref "H5") (pin "3") (pinfunction "3_3") (pintype "unspecified"))
      (node (ref "H6") (pin "1") (pinfunction "1_1") (pintype "unspecified"))
      (node (ref "R1") (pin "2") (pinfunction "2_2") (pintype "unspecified"))
      (node (ref "R2") (pin "2") (pinfunction "2_2") (pintype "unspecified"))
      (node (ref "R3") (pin "2") (pinfunction "2_2") (pintype "unspecified"))
      (node (ref "R4") (pin "2") (pinfunction "2_2") (pintype "unspecified"))
      (node (ref "R5") (pin "2") (pinfunction "2_2") (pintype "unspecified"))
      (node (ref "R6") (pin "2") (pinfunction "2_2") (pintype "unspecified"))
      (node (ref "R7") (pin "2") (pinfunction "2_2") (pintype "unspecified"))
      (node (ref "R8") (pin "2") (pinfunction "2_2") (pintype "unspecified"))
      (node (ref "R9") (pin "1") (pinfunction "1_1") (pintype "unspecified"))
      (node (ref "SW1") (pin "4") (pinfunction "4_4") (pintype "unspecified"))
      (node (ref "SW2") (pin "4") (pinfunction "4_4") (pintype "unspecified"))
      (node (ref "SW3") (pin "4") (pinfunction "4_4") (pintype "unspecified"))
      (node (ref "U1") (pin "16") (pinfunction "VCC_16") (pintype "input"))
      (node (ref "U2") (pin "20") (pinfunction "VCC_20") (pintype "unspecified"))
      (node (ref "USB1") (pin "1") (pinfunction "VBUS_1") (pintype "unspecified"))
    )
    (net (code "43") (name "unconnected-(SW1-Pad1)") (class "Default")
      (node (ref "SW1") (pin "1") (pinfunction "1_1") (pintype "unspecified+no_connect"))
    )
    (net (code "44") (name "unconnected-(SW1-Pad2)") (class "Default")
      (node (ref "SW1") (pin "2") (pinfunction "2_2") (pintype "unspecified+no_connect"))
    )
    (net (code "45") (name "unconnected-(SW1-Pad3)") (class "Default")
      (node (ref "SW1") (pin "3") (pinfunction "3_3") (pintype "unspecified+no_connect"))
    )
    (net (code "46") (name "unconnected-(SW2-Pad1)") (class "Default")
      (node (ref "SW2") (pin "1") (pinfunction "1_1") (pintype "unspecified+no_connect"))
    )
    (net (code "47") (name "unconnected-(SW2-Pad2)") (class "Default")
      (node (ref "SW2") (pin "2") (pinfunction "2_2") (pintype "unspecified+no_connect"))
    )
    (net (code "48") (name "unconnected-(SW2-Pad3)") (class "Default")
      (node (ref "SW2") (pin "3") (pinfunction "3_3") (pintype "unspecified+no_connect"))
    )
    (net (code "49") (name "unconnected-(SW3-Pad1)") (class "Default")
      (node (ref "SW3") (pin "1") (pinfunction "1_1") (pintype "unspecified+no_connect"))
    )
    (net (code "50") (name "unconnected-(SW3-Pad2)") (class "Default")
      (node (ref "SW3") (pin "2") (pinfunction "2_2") (pintype "unspecified+no_connect"))
    )
    (net (code "51") (name "unconnected-(SW3-Pad3)") (class "Default")
      (node (ref "SW3") (pin "3") (pinfunction "3_3") (pintype "unspecified+no_connect"))
    )
    (net (code "52") (name "unconnected-(USB1-D+-Pad3)") (class "Default")
      (node (ref "USB1") (pin "3") (pinfunction "D+_3") (pintype "unspecified+no_connect"))
    )
    (net (code "53") (name "unconnected-(USB1-D--Pad2)") (class "Default")
      (node (ref "USB1") (pin "2") (pinfunction "D-_2") (pintype "unspecified+no_connect"))
    )
    (net (code "54") (name "unconnected-(USB1-ID-Pad4)") (class "Default")
      (node (ref "USB1") (pin "4") (pinfunction "ID_4") (pintype "unspecified+no_connect"))
    )
  )
)
